# INPUT_PROTECTION.net
KiCad netlist of a schematic drawn in Altium Designer
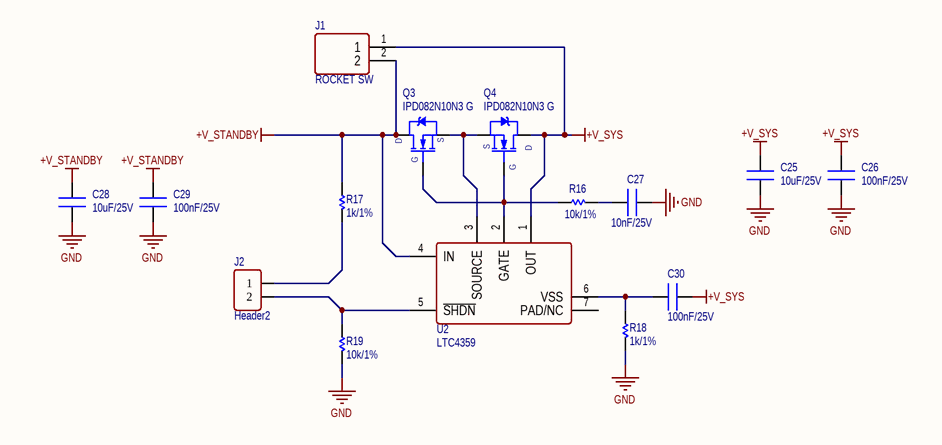
[diagram p0: INPUT_PROTECTION.SchDoc]

(export (version "E")
  (design (tool "Eeschema 10.0.6"))
  (components
    (comp (ref "C25")
      (value "10uF/25V")
      (footprint "CN-SMD-0603")
      (description "CAP CER 10UF 25V X5R 0603")
      (libsource (lib "Library") (part "CN"))
    )
    (comp (ref "C26")
      (value "100nF/25V")
      (footprint "CN-SMD-0603")
      (description "CAP CER 0.1UF 25V X7R 0603")
      (libsource (lib "Library") (part "CN"))
    )
    (comp (ref "C27")
      (value "10nF/25V")
      (footprint "CN-SMD-0603")
      (description "CAP CER 10000PF 25V X7R 0603")
      (libsource (lib "Library") (part "CN"))
    )
    (comp (ref "C28")
      (value "10uF/25V")
      (footprint "CN-SMD-0603")
      (description "CAP CER 10UF 25V X5R 0603")
      (libsource (lib "Library") (part "CN"))
    )
    (comp (ref "C29")
      (value "100nF/25V")
      (footprint "CN-SMD-0603")
      (description "CAP CER 0.1UF 25V X7R 0603")
      (libsource (lib "Library") (part "CN"))
    )
    (comp (ref "C30")
      (value "100nF/25V")
      (footprint "CN-SMD-0603")
      (description "CAP CER 0.1UF 25V X7R 0603")
      (libsource (lib "Library") (part "CN"))
    )
    (comp (ref "J1")
      (value "ROCKET SW")
      (footprint "S2P-VH(LF)(SN)")
      (description "CONN HEADER R/A 2POS 3.96MM")
      (libsource (lib "Library") (part "KF2"))
    )
    (comp (ref "J2")
      (value "Header2")
      (footprint "XH2.54-2-DIP")
      (description "Connector 2")
      (fields
        (field (name "MANUFACTURER") "Würth Elektronik eiSos GmbH")
        (field (name "PARTNO") "613002143121")
        (field (name "CREATED BY") "Karrer Zheng")
      )
      (libsource (lib "Library") (part "Header2"))
    )
    (comp (ref "Q3")
      (value "IPD082N10N3 G")
      (footprint "TO252-123")
      (description "MOSFET N-CH 100V 80A DPAK")
      (libsource (lib "Library") (part "FDD8870"))
    )
    (comp (ref "Q4")
      (value "IPD082N10N3 G")
      (footprint "TO252-123")
      (description "MOSFET N-CH 100V 80A DPAK")
      (libsource (lib "Library") (part "FDD8870"))
    )
    (comp (ref "R16")
      (value "10k/1%")
      (footprint "RES-SMD-0603")
      (description "RES SMD 10K OHM 1% 1/10W 0603")
      (fields
        (field (name "MANUFACTURER") "Generic Components")
        (field (name "PUBLISHER") "Altium Hobart Technology Centre")
      )
      (libsource (lib "Library") (part "Res-SMD"))
    )
    (comp (ref "R17")
      (value "1k/1%")
      (footprint "RES-SMD-0603")
      (description "RES SMD 1K OHM 1% 1/10W 0603")
      (fields
        (field (name "MANUFACTURER") "Generic Components")
        (field (name "PUBLISHER") "Altium Hobart Technology Centre")
      )
      (libsource (lib "Library") (part "Res-SMD"))
    )
    (comp (ref "R18")
      (value "1k/1%")
      (footprint "RES-SMD-0603")
      (description "RES SMD 1K OHM 1% 1/10W 0603")
      (fields
        (field (name "MANUFACTURER") "Generic Components")
        (field (name "PUBLISHER") "Altium Hobart Technology Centre")
      )
      (libsource (lib "Library") (part "Res-SMD"))
    )
    (comp (ref "R19")
      (value "10k/1%")
      (footprint "RES-SMD-0603")
      (description "RES SMD 10K OHM 1% 1/10W 0603")
      (fields
        (field (name "MANUFACTURER") "Generic Components")
        (field (name "PUBLISHER") "Altium Hobart Technology Centre")
      )
      (libsource (lib "Library") (part "Res-SMD"))
    )
    (comp (ref "U2")
      (value "LTC4359")
      (footprint "VSSOP8")
      (description "IC OR CTRLR N+1 8MSOP")
      (libsource (lib "Library") (part "LTC4359"))
    )
  )
  (nets
    (net (code "1") (name "+V_STANDBY") (class "Default")
      (node (ref "C28") (pin "2") (pinfunction "2_2") (pintype "passive"))
      (node (ref "C29") (pin "2") (pinfunction "2_2") (pintype "passive"))
      (node (ref "J1") (pin "2") (pinfunction "2_2") (pintype "passive"))
      (node (ref "Q3") (pin "2") (pinfunction "D_2") (pintype "passive"))
      (node (ref "R17") (pin "1") (pinfunction "1_1") (pintype "passive"))
      (node (ref "U2") (pin "4") (pinfunction "IN_4") (pintype "passive"))
    )
    (net (code "2") (name "+V_SYS") (class "Default")
      (node (ref "C25") (pin "2") (pinfunction "2_2") (pintype "passive"))
      (node (ref "C26") (pin "2") (pinfunction "2_2") (pintype "passive"))
      (node (ref "C30") (pin "2") (pinfunction "2_2") (pintype "passive"))
      (node (ref "J1") (pin "1") (pinfunction "1_1") (pintype "passive"))
      (node (ref "Q4") (pin "2") (pinfunction "D_2") (pintype "passive"))
      (node (ref "U2") (pin "1") (pinfunction "OUT_1") (pintype "passive"))
    )
    (net (code "3") (name "GND") (class "Default")
      (node (ref "C25") (pin "1") (pinfunction "1_1") (pintype "passive"))
      (node (ref "C26") (pin "1") (pinfunction "1_1") (pintype "passive"))
      (node (ref "C27") (pin "1") (pinfunction "1_1") (pintype "passive"))
      (node (ref "C28") (pin "1") (pinfunction "1_1") (pintype "passive"))
      (node (ref "C29") (pin "1") (pinfunction "1_1") (pintype "passive"))
      (node (ref "R18") (pin "2") (pinfunction "2_2") (pintype "passive"))
      (node (ref "R19") (pin "2") (pinfunction "2_2") (pintype "passive"))
    )
    (net (code "4") (name "Net-(C27-Pad2)") (class "Default")
      (node (ref "C27") (pin "2") (pinfunction "2_2") (pintype "passive"))
      (node (ref "R16") (pin "2") (pinfunction "2_2") (pintype "passive"))
    )
    (net (code "5") (name "Net-(J2-Pad1)") (class "Default")
      (node (ref "J2") (pin "1") (pinfunction "1_1") (pintype "passive"))
      (node (ref "R17") (pin "2") (pinfunction "2_2") (pintype "passive"))
    )
    (net (code "6") (name "Net-(Q3-G)") (class "Default")
      (node (ref "Q3") (pin "1") (pinfunction "G_1") (pintype "passive"))
      (node (ref "Q4") (pin "1") (pinfunction "G_1") (pintype "passive"))
      (node (ref "R16") (pin "1") (pinfunction "1_1") (pintype "passive"))
      (node (ref "U2") (pin "2") (pinfunction "GATE_2") (pintype "passive"))
    )
    (net (code "7") (name "Net-(Q3-S)") (class "Default")
      (node (ref "Q3") (pin "3") (pinfunction "S_3") (pintype "passive"))
      (node (ref "Q4") (pin "3") (pinfunction "S_3") (pintype "passive"))
      (node (ref "U2") (pin "3") (pinfunction "SOURCE_3") (pintype "passive"))
    )
    (net (code "8") (name "Net-(U2-VSS)") (class "Default")
      (node (ref "C30") (pin "1") (pinfunction "1_1") (pintype "passive"))
      (node (ref "R18") (pin "1") (pinfunction "1_1") (pintype "passive"))
      (node (ref "U2") (pin "6") (pinfunction "VSS_6") (pintype "passive"))
    )
    (net (code "9") (name "Net-(U2-~{SHDN})") (class "Default")
      (node (ref "J2") (pin "2") (pinfunction "2_2") (pintype "passive"))
      (node (ref "R19") (pin "1") (pinfunction "1_1") (pintype "passive"))
      (node (ref "U2") (pin "5") (pinfunction "~{SHDN}_5") (pintype "passive"))
    )
    (net (code "10") (name "unconnected-(U2-PAD{slash}NC-Pad7)") (class "Default")
      (node (ref "U2") (pin "7") (pinfunction "PAD/NC_7") (pintype "passive"))
    )
  )
)
